# Adafruit_Motor_Bonnet_Rev_B.net
KiCad netlist of a schematic drawn in EAGLE
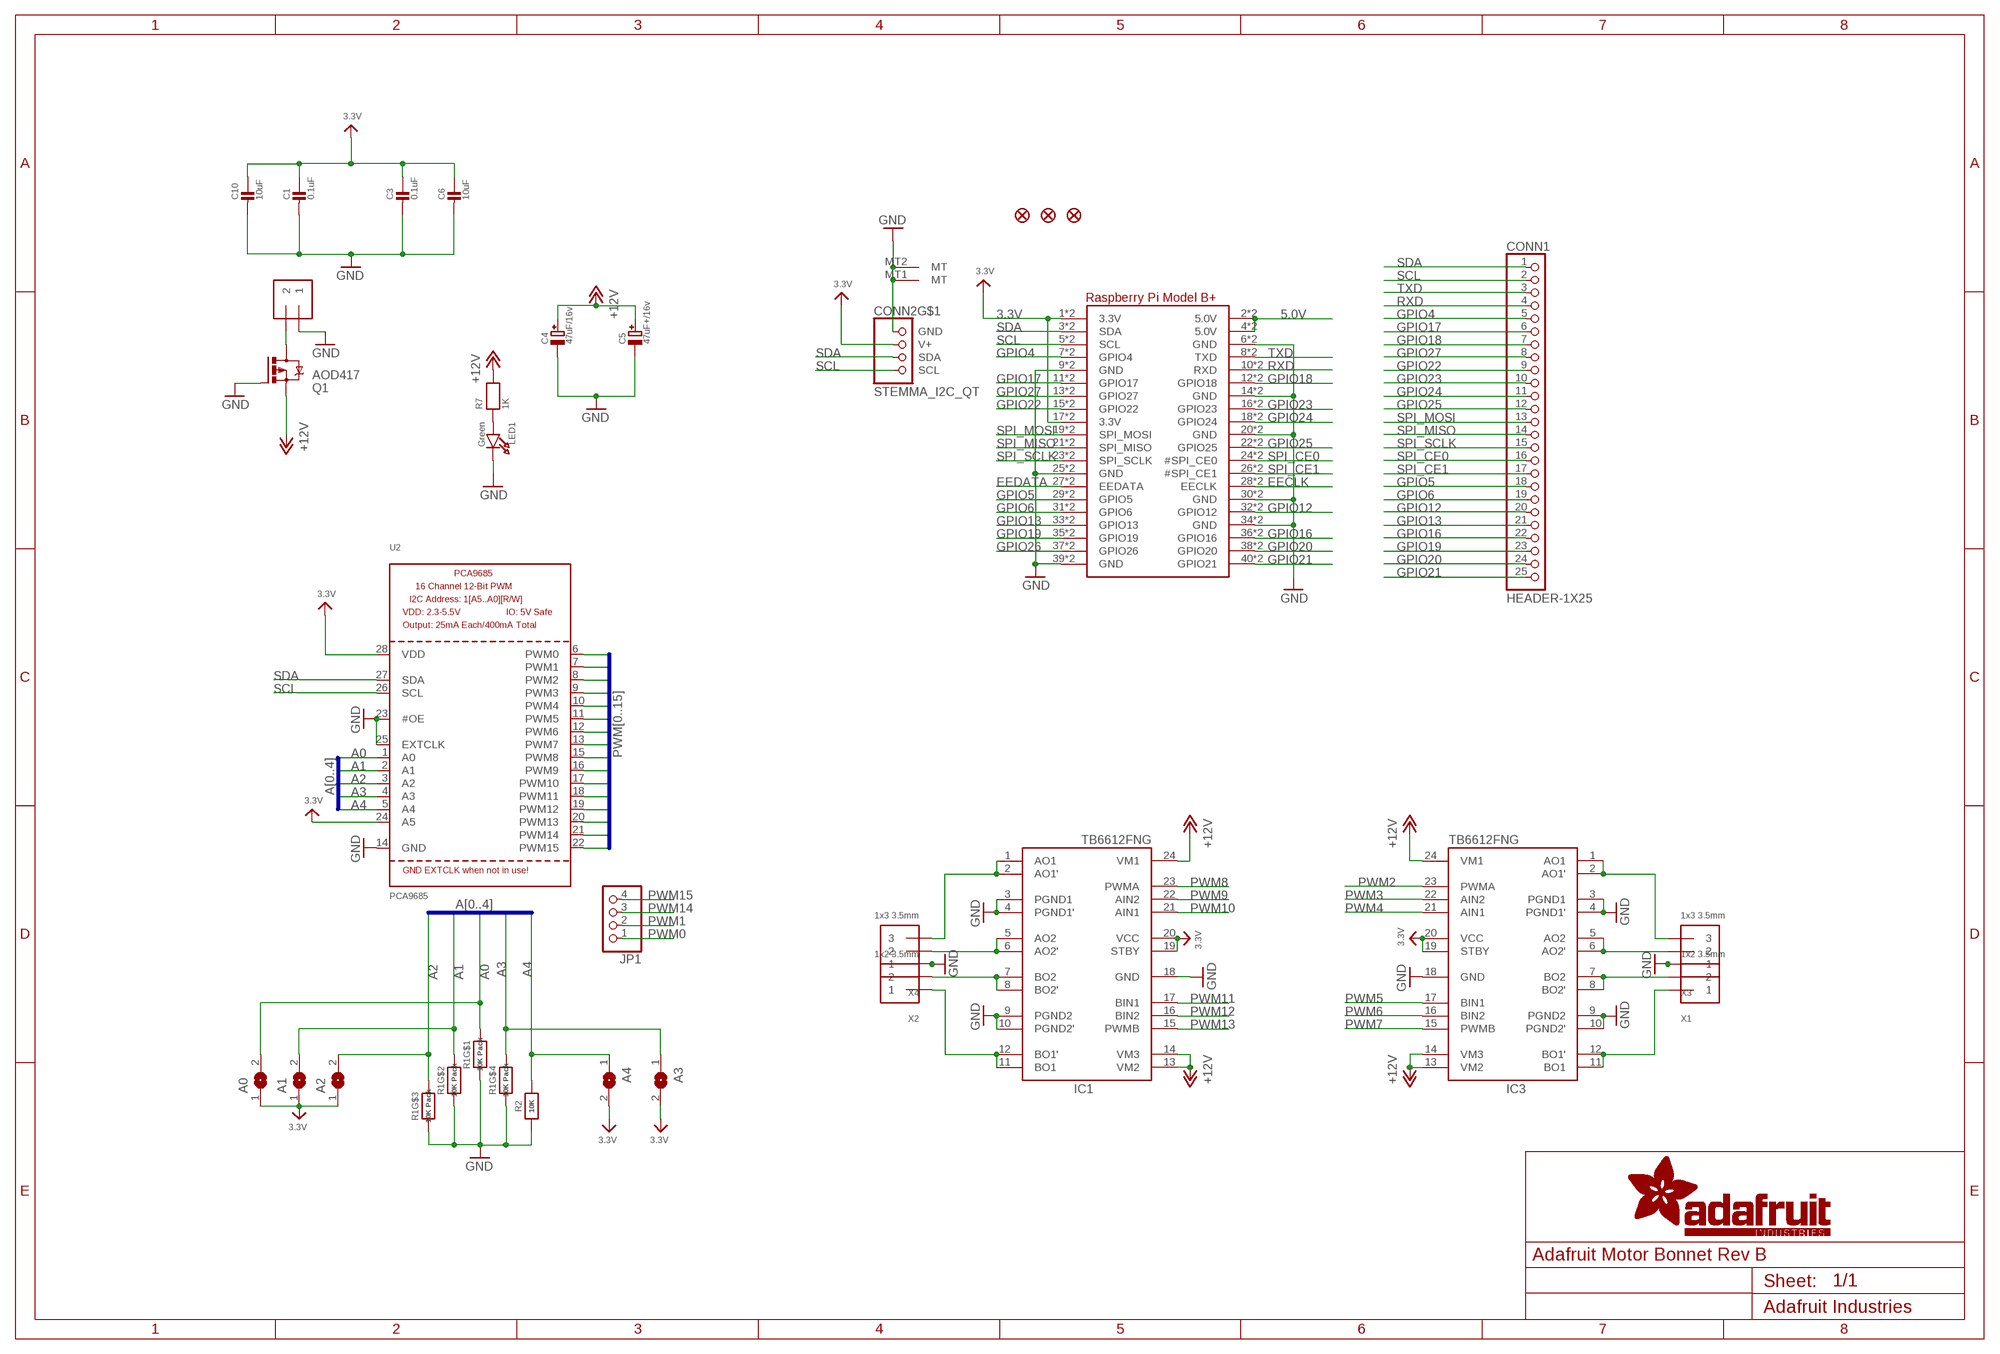
[diagram p0: schematic, sheet 1]

(export (version "E")
  (design (tool "Eeschema 10.0.6"))
  (components
    (comp (ref "A0")
      (value "SOLDERJUMPERREFLOW_NOPASTE")
      (footprint "eagle-import:SOLDERJUMPER_REFLOW_NOPASTE")
      (libsource (lib "eagle-import") (part "SOLDERJUMPERREFLOW_NOPASTE"))
    )
    (comp (ref "A1")
      (value "SOLDERJUMPERREFLOW_NOPASTE")
      (footprint "eagle-import:SOLDERJUMPER_REFLOW_NOPASTE")
      (libsource (lib "eagle-import") (part "SOLDERJUMPERREFLOW_NOPASTE"))
    )
    (comp (ref "A2")
      (value "SOLDERJUMPERREFLOW_NOPASTE")
      (footprint "eagle-import:SOLDERJUMPER_REFLOW_NOPASTE")
      (libsource (lib "eagle-import") (part "SOLDERJUMPERREFLOW_NOPASTE"))
    )
    (comp (ref "A3")
      (value "SOLDERJUMPERREFLOW_NOPASTE")
      (footprint "eagle-import:SOLDERJUMPER_REFLOW_NOPASTE")
      (libsource (lib "eagle-import") (part "SOLDERJUMPERREFLOW_NOPASTE"))
    )
    (comp (ref "A4")
      (value "SOLDERJUMPERREFLOW_NOPASTE")
      (footprint "eagle-import:SOLDERJUMPER_REFLOW_NOPASTE")
      (libsource (lib "eagle-import") (part "SOLDERJUMPERREFLOW_NOPASTE"))
    )
    (comp (ref "C1")
      (value "0.1uF")
      (footprint "eagle-import:0603-NO")
      (libsource (lib "eagle-import") (part "CAP_CERAMIC0603_NO"))
    )
    (comp (ref "C3")
      (value "0.1uF")
      (footprint "eagle-import:0603-NO")
      (libsource (lib "eagle-import") (part "CAP_CERAMIC0603_NO"))
    )
    (comp (ref "C4")
      (value "47uF/16v")
      (footprint "eagle-import:PANASONIC_C")
      (libsource (lib "eagle-import") (part "CAP_ELECTROLYTICPANASONIC_C"))
    )
    (comp (ref "C5")
      (value "47uF+/16v")
      (footprint "eagle-import:PANASONIC_C")
      (libsource (lib "eagle-import") (part "CAP_ELECTROLYTICPANASONIC_C"))
    )
    (comp (ref "C6")
      (value "10uF")
      (footprint "eagle-import:0805-NO")
      (libsource (lib "eagle-import") (part "CAP_CERAMIC0805-NOOUTLINE"))
    )
    (comp (ref "C10")
      (value "10uF")
      (footprint "eagle-import:0805-NO")
      (libsource (lib "eagle-import") (part "CAP_CERAMIC0805-NOOUTLINE"))
    )
    (comp (ref "CONN1")
      (value "HEADER-1X25")
      (footprint "eagle-import:1X25_ROUND_70MIL")
      (libsource (lib "eagle-import") (part "HEADER-1X25"))
    )
    (comp (ref "CONN2")
      (value "STEMMA_I2C_QT")
      (footprint "eagle-import:JST_SH4")
      (libsource (lib "eagle-import") (part "STEMMA_I2C_QT"))
    )
    (comp (ref "FID1")
      (value "FIDUCIAL_1MM")
      (footprint "eagle-import:FIDUCIAL_1MM")
      (libsource (lib "eagle-import") (part "FIDUCIAL_1MM"))
    )
    (comp (ref "FID2")
      (value "FIDUCIAL_1MM")
      (footprint "eagle-import:FIDUCIAL_1MM")
      (libsource (lib "eagle-import") (part "FIDUCIAL_1MM"))
    )
    (comp (ref "FID3")
      (value "FIDUCIAL_1MM")
      (footprint "eagle-import:FIDUCIAL_1MM")
      (libsource (lib "eagle-import") (part "FIDUCIAL_1MM"))
    )
    (comp (ref "IC1")
      (value "TB6612FNG")
      (footprint "eagle-import:SSOP24")
      (libsource (lib "eagle-import") (part "TB6612FNG"))
    )
    (comp (ref "IC3")
      (value "TB6612FNG")
      (footprint "eagle-import:SSOP24")
      (libsource (lib "eagle-import") (part "TB6612FNG"))
    )
    (comp (ref "JP1")
      (value "HEADER-1X4ROUND")
      (footprint "eagle-import:1X04_ROUND")
      (libsource (lib "eagle-import") (part "HEADER-1X4ROUND"))
    )
    (comp (ref "LED1")
      (value "Green")
      (footprint "eagle-import:CHIPLED_0805_NOOUTLINE")
      (libsource (lib "eagle-import") (part "LED0805_NOOUTLINE"))
    )
    (comp (ref "MPOWER")
      (value "1x2 3.5mm")
      (footprint "eagle-import:TERMBLOCK_1X2-3.5MM")
      (fields (field (name "ROT") "0"))
      (libsource (lib "eagle-import") (part "TERMBLOCK_1X2_3.5MM"))
    )
    (comp (ref "Q1")
      (value "AOD417")
      (footprint "eagle-import:D-PAK_TO252AA")
      (libsource (lib "eagle-import") (part "IRF?5305R"))
    )
    (comp (ref "R1")
      (value "10K Pack")
      (footprint "eagle-import:RESPACK_4X0603")
      (libsource (lib "eagle-import") (part "RESISTOR_4PACK"))
    )
    (comp (ref "R2")
      (value "10K")
      (footprint "eagle-import:0603-NO")
      (libsource (lib "eagle-import") (part "RESISTOR_0603_NOOUT"))
    )
    (comp (ref "R7")
      (value "1K")
      (footprint "eagle-import:0603-NO")
      (libsource (lib "eagle-import") (part "RESISTOR_0603_NOOUT"))
    )
    (comp (ref "RPI1")
      (value "RASPBERRYPI_BPLUS_BONNET_THMSMT")
      (footprint "eagle-import:PI_BONNET_THMSMT")
      (libsource (lib "eagle-import") (part "RASPBERRYPI_BPLUS_BONNET_THMSMT"))
    )
    (comp (ref "U2")
      (value "PCA9685")
      (footprint "eagle-import:TSSOP28")
      (libsource (lib "eagle-import") (part "PCA9685"))
    )
    (comp (ref "X1")
      (value "1x2 3.5mm")
      (footprint "eagle-import:TERMBLOCK_1X2-3.5MM")
      (fields (field (name "ROT") "0"))
      (libsource (lib "eagle-import") (part "TERMBLOCK_1X2_3.5MM"))
    )
    (comp (ref "X2")
      (value "1x2 3.5mm")
      (footprint "eagle-import:TERMBLOCK_1X2-3.5MM")
      (fields (field (name "ROT") "0"))
      (libsource (lib "eagle-import") (part "TERMBLOCK_1X2_3.5MM"))
    )
    (comp (ref "X3")
      (value "1x3 3.5mm")
      (footprint "eagle-import:TERMBLOCK_1X3-3.5MM")
      (libsource (lib "eagle-import") (part "TERMBLOCK_1X3"))
    )
    (comp (ref "X4")
      (value "1x3 3.5mm")
      (footprint "eagle-import:TERMBLOCK_1X3-3.5MM")
      (libsource (lib "eagle-import") (part "TERMBLOCK_1X3"))
    )
  )
  (nets
    (net (code "1") (name "+12V") (class "Default")
      (node (ref "C4") (pin "+") (pinfunction "+_+") (pintype "passive"))
      (node (ref "C5") (pin "+") (pinfunction "+_+") (pintype "passive"))
      (node (ref "IC1") (pin "13") (pinfunction "VM2_13") (pintype "power_in"))
      (node (ref "IC1") (pin "14") (pinfunction "VM3_14") (pintype "power_in"))
      (node (ref "IC1") (pin "24") (pinfunction "VM1_24") (pintype "power_in"))
      (node (ref "IC3") (pin "13") (pinfunction "VM2_13") (pintype "power_in"))
      (node (ref "IC3") (pin "14") (pinfunction "VM3_14") (pintype "power_in"))
      (node (ref "IC3") (pin "24") (pinfunction "VM1_24") (pintype "power_in"))
      (node (ref "Q1") (pin "3") (pinfunction "S_3") (pintype "passive"))
      (node (ref "R7") (pin "2") (pinfunction "2_2") (pintype "passive"))
    )
    (net (code "2") (name "/5.0V") (class "Default")
      (node (ref "RPI1") (pin "2") (pinfunction "5.0V_2") (pintype "power_in"))
      (node (ref "RPI1") (pin "4") (pinfunction "5.0V_4") (pintype "power_in"))
      (node (ref "RPI1") (pin "S2") (pinfunction "5.0V_S2") (pintype "power_in"))
      (node (ref "RPI1") (pin "S4") (pinfunction "5.0V_S4") (pintype "power_in"))
    )
    (net (code "3") (name "/A0") (class "Default")
      (node (ref "A0") (pin "2") (pinfunction "2_2") (pintype "passive"))
      (node (ref "R1") (pin "8") (pinfunction "2_8") (pintype "passive"))
      (node (ref "U2") (pin "1") (pinfunction "A0_1") (pintype "bidirectional"))
    )
    (net (code "4") (name "/A1") (class "Default")
      (node (ref "A1") (pin "2") (pinfunction "2_2") (pintype "passive"))
      (node (ref "R1") (pin "7") (pinfunction "2_7") (pintype "passive"))
      (node (ref "U2") (pin "2") (pinfunction "A1_2") (pintype "bidirectional"))
    )
    (net (code "5") (name "/A2") (class "Default")
      (node (ref "A2") (pin "2") (pinfunction "2_2") (pintype "passive"))
      (node (ref "R1") (pin "6") (pinfunction "2_6") (pintype "passive"))
      (node (ref "U2") (pin "3") (pinfunction "A2_3") (pintype "bidirectional"))
    )
    (net (code "6") (name "/A3") (class "Default")
      (node (ref "A3") (pin "1") (pinfunction "1_1") (pintype "passive"))
      (node (ref "R1") (pin "5") (pinfunction "2_5") (pintype "passive"))
      (node (ref "U2") (pin "4") (pinfunction "A3_4") (pintype "bidirectional"))
    )
    (net (code "7") (name "/A4") (class "Default")
      (node (ref "A4") (pin "1") (pinfunction "1_1") (pintype "passive"))
      (node (ref "R2") (pin "2") (pinfunction "2_2") (pintype "passive"))
      (node (ref "U2") (pin "5") (pinfunction "A4_5") (pintype "bidirectional"))
    )
    (net (code "9") (name "/EECLK") (class "Default")
      (node (ref "RPI1") (pin "28") (pinfunction "EECLK_28") (pintype "bidirectional"))
      (node (ref "RPI1") (pin "S28") (pinfunction "EECLK_S28") (pintype "bidirectional"))
    )
    (net (code "10") (name "/EEDATA") (class "Default")
      (node (ref "RPI1") (pin "27") (pinfunction "EEDATA_27") (pintype "bidirectional"))
      (node (ref "RPI1") (pin "S27") (pinfunction "EEDATA_S27") (pintype "bidirectional"))
    )
    (net (code "11") (name "/GPIO4") (class "Default")
      (node (ref "CONN1") (pin "5") (pinfunction "5_5") (pintype "passive"))
      (node (ref "RPI1") (pin "7") (pinfunction "GPIO4_7") (pintype "bidirectional"))
      (node (ref "RPI1") (pin "S7") (pinfunction "GPIO4_S7") (pintype "bidirectional"))
    )
    (net (code "12") (name "/GPIO5") (class "Default")
      (node (ref "CONN1") (pin "18") (pinfunction "18_18") (pintype "passive"))
      (node (ref "RPI1") (pin "29") (pinfunction "GPIO5_29") (pintype "bidirectional"))
      (node (ref "RPI1") (pin "S29") (pinfunction "GPIO5_S29") (pintype "bidirectional"))
    )
    (net (code "13") (name "/GPIO6") (class "Default")
      (node (ref "CONN1") (pin "19") (pinfunction "19_19") (pintype "passive"))
      (node (ref "RPI1") (pin "31") (pinfunction "GPIO6_31") (pintype "bidirectional"))
      (node (ref "RPI1") (pin "S31") (pinfunction "GPIO6_S31") (pintype "bidirectional"))
    )
    (net (code "14") (name "/GPIO12") (class "Default")
      (node (ref "CONN1") (pin "20") (pinfunction "20_20") (pintype "passive"))
      (node (ref "RPI1") (pin "32") (pinfunction "GPIO12_32") (pintype "bidirectional"))
      (node (ref "RPI1") (pin "S32") (pinfunction "GPIO12_S32") (pintype "bidirectional"))
    )
    (net (code "15") (name "/GPIO13") (class "Default")
      (node (ref "CONN1") (pin "21") (pinfunction "21_21") (pintype "passive"))
      (node (ref "RPI1") (pin "33") (pinfunction "GPIO13_33") (pintype "bidirectional"))
      (node (ref "RPI1") (pin "S33") (pinfunction "GPIO13_S33") (pintype "bidirectional"))
    )
    (net (code "16") (name "/GPIO16") (class "Default")
      (node (ref "CONN1") (pin "22") (pinfunction "22_22") (pintype "passive"))
      (node (ref "RPI1") (pin "36") (pinfunction "GPIO16_36") (pintype "bidirectional"))
      (node (ref "RPI1") (pin "S36") (pinfunction "GPIO16_S36") (pintype "bidirectional"))
    )
    (net (code "17") (name "/GPIO17") (class "Default")
      (node (ref "CONN1") (pin "6") (pinfunction "6_6") (pintype "passive"))
      (node (ref "RPI1") (pin "11") (pinfunction "GPIO17_11") (pintype "bidirectional"))
      (node (ref "RPI1") (pin "S11") (pinfunction "GPIO17_S11") (pintype "bidirectional"))
    )
    (net (code "18") (name "/GPIO18") (class "Default")
      (node (ref "CONN1") (pin "7") (pinfunction "7_7") (pintype "passive"))
      (node (ref "RPI1") (pin "12") (pinfunction "GPIO18_12") (pintype "bidirectional"))
      (node (ref "RPI1") (pin "S12") (pinfunction "GPIO18_S12") (pintype "bidirectional"))
    )
    (net (code "19") (name "/GPIO19") (class "Default")
      (node (ref "CONN1") (pin "23") (pinfunction "23_23") (pintype "passive"))
      (node (ref "RPI1") (pin "35") (pinfunction "GPIO19_35") (pintype "bidirectional"))
      (node (ref "RPI1") (pin "S35") (pinfunction "GPIO19_S35") (pintype "bidirectional"))
    )
    (net (code "20") (name "/GPIO20") (class "Default")
      (node (ref "CONN1") (pin "24") (pinfunction "24_24") (pintype "passive"))
      (node (ref "RPI1") (pin "38") (pinfunction "GPIO20_38") (pintype "bidirectional"))
      (node (ref "RPI1") (pin "S38") (pinfunction "GPIO20_S38") (pintype "bidirectional"))
    )
    (net (code "21") (name "/GPIO21") (class "Default")
      (node (ref "CONN1") (pin "25") (pinfunction "25_25") (pintype "passive"))
      (node (ref "RPI1") (pin "40") (pinfunction "GPIO21_40") (pintype "bidirectional"))
      (node (ref "RPI1") (pin "S40") (pinfunction "GPIO21_S40") (pintype "bidirectional"))
    )
    (net (code "22") (name "/GPIO22") (class "Default")
      (node (ref "CONN1") (pin "9") (pinfunction "9_9") (pintype "passive"))
      (node (ref "RPI1") (pin "15") (pinfunction "GPIO22_15") (pintype "bidirectional"))
      (node (ref "RPI1") (pin "S15") (pinfunction "GPIO22_S15") (pintype "bidirectional"))
    )
    (net (code "23") (name "/GPIO23") (class "Default")
      (node (ref "CONN1") (pin "10") (pinfunction "10_10") (pintype "passive"))
      (node (ref "RPI1") (pin "16") (pinfunction "GPIO23_16") (pintype "bidirectional"))
      (node (ref "RPI1") (pin "S16") (pinfunction "GPIO23_S16") (pintype "bidirectional"))
    )
    (net (code "24") (name "/GPIO24") (class "Default")
      (node (ref "CONN1") (pin "11") (pinfunction "11_11") (pintype "passive"))
      (node (ref "RPI1") (pin "18") (pinfunction "GPIO24_18") (pintype "bidirectional"))
      (node (ref "RPI1") (pin "S18") (pinfunction "GPIO24_S18") (pintype "bidirectional"))
    )
    (net (code "25") (name "/GPIO25") (class "Default")
      (node (ref "CONN1") (pin "12") (pinfunction "12_12") (pintype "passive"))
      (node (ref "RPI1") (pin "22") (pinfunction "GPIO25_22") (pintype "bidirectional"))
      (node (ref "RPI1") (pin "S22") (pinfunction "GPIO25_S22") (pintype "bidirectional"))
    )
    (net (code "26") (name "/GPIO26") (class "Default")
      (node (ref "RPI1") (pin "37") (pinfunction "GPIO26_37") (pintype "bidirectional"))
      (node (ref "RPI1") (pin "S37") (pinfunction "GPIO26_S37") (pintype "bidirectional"))
    )
    (net (code "27") (name "/GPIO27") (class "Default")
      (node (ref "CONN1") (pin "8") (pinfunction "8_8") (pintype "passive"))
      (node (ref "RPI1") (pin "13") (pinfunction "GPIO27_13") (pintype "bidirectional"))
      (node (ref "RPI1") (pin "S13") (pinfunction "GPIO27_S13") (pintype "bidirectional"))
    )
    (net (code "28") (name "/PWM0") (class "Default")
      (node (ref "JP1") (pin "1") (pinfunction "1_1") (pintype "passive"))
      (node (ref "U2") (pin "6") (pinfunction "PWM0_6") (pintype "output"))
    )
    (net (code "29") (name "/PWM1") (class "Default")
      (node (ref "JP1") (pin "2") (pinfunction "2_2") (pintype "passive"))
      (node (ref "U2") (pin "7") (pinfunction "PWM1_7") (pintype "output"))
    )
    (net (code "30") (name "/PWM2") (class "Default")
      (node (ref "IC3") (pin "23") (pinfunction "PWMA_23") (pintype "input"))
      (node (ref "U2") (pin "8") (pinfunction "PWM2_8") (pintype "output"))
    )
    (net (code "31") (name "/PWM3") (class "Default")
      (node (ref "IC3") (pin "22") (pinfunction "AIN2_22") (pintype "input"))
      (node (ref "U2") (pin "9") (pinfunction "PWM3_9") (pintype "output"))
    )
    (net (code "32") (name "/PWM4") (class "Default")
      (node (ref "IC3") (pin "21") (pinfunction "AIN1_21") (pintype "input"))
      (node (ref "U2") (pin "10") (pinfunction "PWM4_10") (pintype "output"))
    )
    (net (code "33") (name "/PWM5") (class "Default")
      (node (ref "IC3") (pin "17") (pinfunction "BIN1_17") (pintype "input"))
      (node (ref "U2") (pin "11") (pinfunction "PWM5_11") (pintype "output"))
    )
    (net (code "34") (name "/PWM6") (class "Default")
      (node (ref "IC3") (pin "16") (pinfunction "BIN2_16") (pintype "input"))
      (node (ref "U2") (pin "12") (pinfunction "PWM6_12") (pintype "output"))
    )
    (net (code "35") (name "/PWM7") (class "Default")
      (node (ref "IC3") (pin "15") (pinfunction "PWMB_15") (pintype "input"))
      (node (ref "U2") (pin "13") (pinfunction "PWM7_13") (pintype "output"))
    )
    (net (code "36") (name "/PWM8") (class "Default")
      (node (ref "IC1") (pin "23") (pinfunction "PWMA_23") (pintype "input"))
      (node (ref "U2") (pin "15") (pinfunction "PWM8_15") (pintype "output"))
    )
    (net (code "37") (name "/PWM9") (class "Default")
      (node (ref "IC1") (pin "22") (pinfunction "AIN2_22") (pintype "input"))
      (node (ref "U2") (pin "16") (pinfunction "PWM9_16") (pintype "output"))
    )
    (net (code "38") (name "/PWM10") (class "Default")
      (node (ref "IC1") (pin "21") (pinfunction "AIN1_21") (pintype "input"))
      (node (ref "U2") (pin "17") (pinfunction "PWM10_17") (pintype "output"))
    )
    (net (code "39") (name "/PWM11") (class "Default")
      (node (ref "IC1") (pin "17") (pinfunction "BIN1_17") (pintype "input"))
      (node (ref "U2") (pin "18") (pinfunction "PWM11_18") (pintype "output"))
    )
    (net (code "40") (name "/PWM12") (class "Default")
      (node (ref "IC1") (pin "16") (pinfunction "BIN2_16") (pintype "input"))
      (node (ref "U2") (pin "19") (pinfunction "PWM12_19") (pintype "output"))
    )
    (net (code "41") (name "/PWM13") (class "Default")
      (node (ref "IC1") (pin "15") (pinfunction "PWMB_15") (pintype "input"))
      (node (ref "U2") (pin "20") (pinfunction "PWM13_20") (pintype "output"))
    )
    (net (code "42") (name "/PWM14") (class "Default")
      (node (ref "JP1") (pin "3") (pinfunction "3_3") (pintype "passive"))
      (node (ref "U2") (pin "21") (pinfunction "PWM14_21") (pintype "output"))
    )
    (net (code "43") (name "/PWM15") (class "Default")
      (node (ref "JP1") (pin "4") (pinfunction "4_4") (pintype "passive"))
      (node (ref "U2") (pin "22") (pinfunction "PWM15_22") (pintype "output"))
    )
    (net (code "45") (name "/RXD") (class "Default")
      (node (ref "CONN1") (pin "4") (pinfunction "4_4") (pintype "passive"))
      (node (ref "RPI1") (pin "10") (pinfunction "RXD_10") (pintype "bidirectional"))
      (node (ref "RPI1") (pin "S10") (pinfunction "RXD_S10") (pintype "bidirectional"))
    )
    (net (code "46") (name "/SCL") (class "Default")
      (node (ref "CONN1") (pin "2") (pinfunction "2_2") (pintype "passive"))
      (node (ref "CONN2") (pin "4") (pinfunction "SCL_4") (pintype "passive"))
      (node (ref "RPI1") (pin "5") (pinfunction "SCL_5") (pintype "bidirectional"))
      (node (ref "RPI1") (pin "S5") (pinfunction "SCL_S5") (pintype "bidirectional"))
      (node (ref "U2") (pin "26") (pinfunction "SCL_26") (pintype "bidirectional"))
    )
    (net (code "47") (name "/SDA") (class "Default")
      (node (ref "CONN1") (pin "1") (pinfunction "1_1") (pintype "passive"))
      (node (ref "CONN2") (pin "3") (pinfunction "SDA_3") (pintype "passive"))
      (node (ref "RPI1") (pin "3") (pinfunction "SDA_3") (pintype "bidirectional"))
      (node (ref "RPI1") (pin "S3") (pinfunction "SDA_S3") (pintype "bidirectional"))
      (node (ref "U2") (pin "27") (pinfunction "SDA_27") (pintype "bidirectional"))
    )
    (net (code "48") (name "/SPI_CE0") (class "Default")
      (node (ref "CONN1") (pin "16") (pinfunction "16_16") (pintype "passive"))
      (node (ref "RPI1") (pin "24") (pinfunction "#SPI_CE0_24") (pintype "bidirectional"))
      (node (ref "RPI1") (pin "S24") (pinfunction "#SPI_CE0_S24") (pintype "bidirectional"))
    )
    (net (code "49") (name "/SPI_CE1") (class "Default")
      (node (ref "CONN1") (pin "17") (pinfunction "17_17") (pintype "passive"))
      (node (ref "RPI1") (pin "26") (pinfunction "#SPI_CE1_26") (pintype "bidirectional"))
      (node (ref "RPI1") (pin "S26") (pinfunction "#SPI_CE1_S26") (pintype "bidirectional"))
    )
    (net (code "50") (name "/SPI_MISO") (class "Default")
      (node (ref "CONN1") (pin "14") (pinfunction "14_14") (pintype "passive"))
      (node (ref "RPI1") (pin "21") (pinfunction "SPI_MISO_21") (pintype "bidirectional"))
      (node (ref "RPI1") (pin "S21") (pinfunction "SPI_MISO_S21") (pintype "bidirectional"))
    )
    (net (code "51") (name "/SPI_MOSI") (class "Default")
      (node (ref "CONN1") (pin "13") (pinfunction "13_13") (pintype "passive"))
      (node (ref "RPI1") (pin "19") (pinfunction "SPI_MOSI_19") (pintype "bidirectional"))
      (node (ref "RPI1") (pin "S19") (pinfunction "SPI_MOSI_S19") (pintype "bidirectional"))
    )
    (net (code "52") (name "/SPI_SCLK") (class "Default")
      (node (ref "CONN1") (pin "15") (pinfunction "15_15") (pintype "passive"))
      (node (ref "RPI1") (pin "23") (pinfunction "SPI_SCLK_23") (pintype "bidirectional"))
      (node (ref "RPI1") (pin "S23") (pinfunction "SPI_SCLK_S23") (pintype "bidirectional"))
    )
    (net (code "53") (name "/TXD") (class "Default")
      (node (ref "CONN1") (pin "3") (pinfunction "3_3") (pintype "passive"))
      (node (ref "RPI1") (pin "8") (pinfunction "TXD_8") (pintype "bidirectional"))
      (node (ref "RPI1") (pin "S8") (pinfunction "TXD_S8") (pintype "bidirectional"))
    )
    (net (code "54") (name "3.3V") (class "Default")
      (node (ref "A0") (pin "1") (pinfunction "1_1") (pintype "passive"))
      (node (ref "A1") (pin "1") (pinfunction "1_1") (pintype "passive"))
      (node (ref "A2") (pin "1") (pinfunction "1_1") (pintype "passive"))
      (node (ref "A3") (pin "2") (pinfunction "2_2") (pintype "passive"))
      (node (ref "A4") (pin "2") (pinfunction "2_2") (pintype "passive"))
      (node (ref "C1") (pin "1") (pinfunction "1_1") (pintype "passive"))
      (node (ref "C10") (pin "1") (pinfunction "1_1") (pintype "passive"))
      (node (ref "C3") (pin "1") (pinfunction "1_1") (pintype "passive"))
      (node (ref "C6") (pin "1") (pinfunction "1_1") (pintype "passive"))
      (node (ref "CONN2") (pin "2") (pinfunction "V+_2") (pintype "passive"))
      (node (ref "IC1") (pin "19") (pinfunction "STBY_19") (pintype "input"))
      (node (ref "IC1") (pin "20") (pinfunction "VCC_20") (pintype "power_in"))
      (node (ref "IC3") (pin "19") (pinfunction "STBY_19") (pintype "input"))
      (node (ref "IC3") (pin "20") (pinfunction "VCC_20") (pintype "power_in"))
      (node (ref "RPI1") (pin "1") (pinfunction "3.3V_1") (pintype "power_in"))
      (node (ref "RPI1") (pin "17") (pinfunction "3.3V_17") (pintype "power_in"))
      (node (ref "RPI1") (pin "S1") (pinfunction "3.3V_S1") (pintype "power_in"))
      (node (ref "RPI1") (pin "S17") (pinfunction "3.3V_S17") (pintype "power_in"))
      (node (ref "U2") (pin "24") (pinfunction "A5_24") (pintype "bidirectional"))
      (node (ref "U2") (pin "28") (pinfunction "VDD_28") (pintype "power_in"))
    )
    (net (code "55") (name "GND") (class "Default")
      (node (ref "C1") (pin "2") (pinfunction "2_2") (pintype "passive"))
      (node (ref "C10") (pin "2") (pinfunction "2_2") (pintype "passive"))
      (node (ref "C3") (pin "2") (pinfunction "2_2") (pintype "passive"))
      (node (ref "C4") (pin "-") (pinfunction "-_-") (pintype "passive"))
      (node (ref "C5") (pin "-") (pinfunction "-_-") (pintype "passive"))
      (node (ref "C6") (pin "2") (pinfunction "2_2") (pintype "passive"))
      (node (ref "CONN2") (pin "1") (pinfunction "GND_1") (pintype "passive"))
      (node (ref "CONN2") (pin "MT1") (pinfunction "MT_MT1") (pintype "bidirectional"))
      (node (ref "CONN2") (pin "MT2") (pinfunction "MT_MT2") (pintype "bidirectional"))
      (node (ref "IC1") (pin "10") (pinfunction "PGND2'_10") (pintype "power_in"))
      (node (ref "IC1") (pin "18") (pinfunction "GND_18") (pintype "power_in"))
      (node (ref "IC1") (pin "3") (pinfunction "PGND1_3") (pintype "power_in"))
      (node (ref "IC1") (pin "4") (pinfunction "PGND1'_4") (pintype "power_in"))
      (node (ref "IC1") (pin "9") (pinfunction "PGND2_9") (pintype "power_in"))
      (node (ref "IC3") (pin "10") (pinfunction "PGND2'_10") (pintype "power_in"))
      (node (ref "IC3") (pin "18") (pinfunction "GND_18") (pintype "power_in"))
      (node (ref "IC3") (pin "3") (pinfunction "PGND1_3") (pintype "power_in"))
      (node (ref "IC3") (pin "4") (pinfunction "PGND1'_4") (pintype "power_in"))
      (node (ref "IC3") (pin "9") (pinfunction "PGND2_9") (pintype "power_in"))
      (node (ref "LED1") (pin "C") (pinfunction "C_C") (pintype "passive"))
      (node (ref "MPOWER") (pin "1") (pinfunction "1_1") (pintype "passive"))
      (node (ref "Q1") (pin "1") (pinfunction "G_1") (pintype "passive"))
      (node (ref "R1") (pin "1") (pinfunction "1_1") (pintype "passive"))
      (node (ref "R1") (pin "2") (pinfunction "1_2") (pintype "passive"))
      (node (ref "R1") (pin "3") (pinfunction "1_3") (pintype "passive"))
      (node (ref "R1") (pin "4") (pinfunction "1_4") (pintype "passive"))
      (node (ref "R2") (pin "1") (pinfunction "1_1") (pintype "passive"))
      (node (ref "RPI1") (pin "14") (pinfunction "GND_14") (pintype "power_in"))
      (node (ref "RPI1") (pin "20") (pinfunction "GND_20") (pintype "power_in"))
      (node (ref "RPI1") (pin "25") (pinfunction "GND_25") (pintype "power_in"))
      (node (ref "RPI1") (pin "30") (pinfunction "GND_30") (pintype "power_in"))
      (node (ref "RPI1") (pin "34") (pinfunction "GND_34") (pintype "power_in"))
      (node (ref "RPI1") (pin "39") (pinfunction "GND_39") (pintype "power_in"))
      (node (ref "RPI1") (pin "6") (pinfunction "GND_6") (pintype "power_in"))
      (node (ref "RPI1") (pin "9") (pinfunction "GND_9") (pintype "power_in"))
      (node (ref "RPI1") (pin "S14") (pinfunction "GND_S14") (pintype "power_in"))
      (node (ref "RPI1") (pin "S20") (pinfunction "GND_S20") (pintype "power_in"))
      (node (ref "RPI1") (pin "S25") (pinfunction "GND_S25") (pintype "power_in"))
      (node (ref "RPI1") (pin "S30") (pinfunction "GND_S30") (pintype "power_in"))
      (node (ref "RPI1") (pin "S34") (pinfunction "GND_S34") (pintype "power_in"))
      (node (ref "RPI1") (pin "S39") (pinfunction "GND_S39") (pintype "power_in"))
      (node (ref "RPI1") (pin "S6") (pinfunction "GND_S6") (pintype "power_in"))
      (node (ref "RPI1") (pin "S9") (pinfunction "GND_S9") (pintype "power_in"))
      (node (ref "U2") (pin "14") (pinfunction "GND_14") (pintype "power_in"))
      (node (ref "U2") (pin "23") (pinfunction "#OE_23") (pintype "input"))
      (node (ref "U2") (pin "25") (pinfunction "EXTCLK_25") (pintype "input"))
      (node (ref "X3") (pin "1") (pinfunction "1_1") (pintype "passive"))
      (node (ref "X4") (pin "1") (pinfunction "1_1") (pintype "passive"))
    )
    (net (code "56") (name "Net-(IC1-AO1')") (class "Default")
      (node (ref "IC1") (pin "1") (pinfunction "AO1_1") (pintype "output"))
      (node (ref "IC1") (pin "2") (pinfunction "AO1'_2") (pintype "output"))
      (node (ref "X4") (pin "3") (pinfunction "3_3") (pintype "passive"))
    )
    (net (code "57") (name "Net-(IC1-AO2')") (class "Default")
      (node (ref "IC1") (pin "5") (pinfunction "AO2_5") (pintype "output"))
      (node (ref "IC1") (pin "6") (pinfunction "AO2'_6") (pintype "output"))
      (node (ref "X4") (pin "2") (pinfunction "2_2") (pintype "passive"))
    )
    (net (code "58") (name "Net-(IC1-BO1')") (class "Default")
      (node (ref "IC1") (pin "11") (pinfunction "BO1_11") (pintype "output"))
      (node (ref "IC1") (pin "12") (pinfunction "BO1'_12") (pintype "output"))
      (node (ref "X2") (pin "1") (pinfunction "1_1") (pintype "passive"))
    )
    (net (code "59") (name "Net-(IC1-BO2')") (class "Default")
      (node (ref "IC1") (pin "7") (pinfunction "BO2_7") (pintype "output"))
      (node (ref "IC1") (pin "8") (pinfunction "BO2'_8") (pintype "output"))
      (node (ref "X2") (pin "2") (pinfunction "2_2") (pintype "passive"))
    )
    (net (code "60") (name "Net-(IC3-AO1')") (class "Default")
      (node (ref "IC3") (pin "1") (pinfunction "AO1_1") (pintype "output"))
      (node (ref "IC3") (pin "2") (pinfunction "AO1'_2") (pintype "output"))
      (node (ref "X3") (pin "3") (pinfunction "3_3") (pintype "passive"))
    )
    (net (code "61") (name "Net-(IC3-AO2')") (class "Default")
      (node (ref "IC3") (pin "5") (pinfunction "AO2_5") (pintype "output"))
      (node (ref "IC3") (pin "6") (pinfunction "AO2'_6") (pintype "output"))
      (node (ref "X3") (pin "2") (pinfunction "2_2") (pintype "passive"))
    )
    (net (code "62") (name "Net-(IC3-BO1')") (class "Default")
      (node (ref "IC3") (pin "11") (pinfunction "BO1_11") (pintype "output"))
      (node (ref "IC3") (pin "12") (pinfunction "BO1'_12") (pintype "output"))
      (node (ref "X1") (pin "1") (pinfunction "1_1") (pintype "passive"))
    )
    (net (code "63") (name "Net-(IC3-BO2')") (class "Default")
      (node (ref "IC3") (pin "7") (pinfunction "BO2_7") (pintype "output"))
      (node (ref "IC3") (pin "8") (pinfunction "BO2'_8") (pintype "output"))
      (node (ref "X1") (pin "2") (pinfunction "2_2") (pintype "passive"))
    )
    (net (code "64") (name "Net-(LED1-PadA)") (class "Default")
      (node (ref "LED1") (pin "A") (pinfunction "A_A") (pintype "passive"))
      (node (ref "R7") (pin "1") (pinfunction "1_1") (pintype "passive"))
    )
    (net (code "65") (name "Net-(Q1-D)") (class "Default")
      (node (ref "MPOWER") (pin "2") (pinfunction "2_2") (pintype "passive"))
      (node (ref "Q1") (pin "4") (pinfunction "D_4") (pintype "passive"))
    )
  )
)
